# decoder.net
KiCad netlist of a schematic drawn in EAGLE
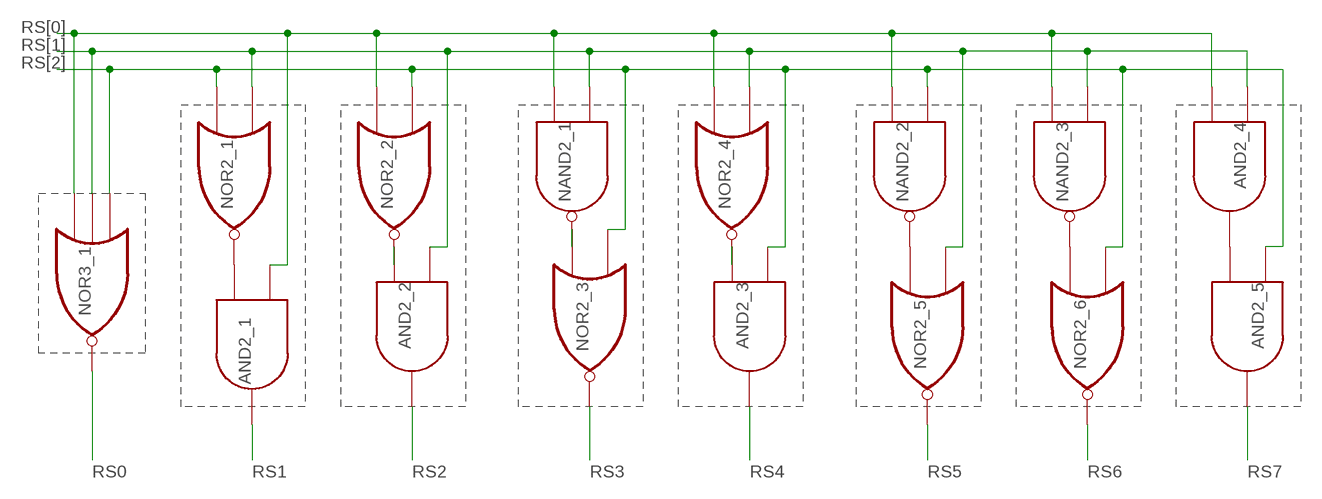
[diagram p0: schematic, sheet 1]

(export (version "E")
  (design (tool "Eeschema 10.0.6"))
  (components
    (comp (ref "AND2_1")
      (value "AND2")
      (footprint "eagle-import:3PIN")
      (libsource (lib "eagle-import") (part "AND2"))
    )
    (comp (ref "AND2_2")
      (value "AND2")
      (footprint "eagle-import:3PIN")
      (libsource (lib "eagle-import") (part "AND2"))
    )
    (comp (ref "AND2_3")
      (value "AND2")
      (footprint "eagle-import:3PIN")
      (libsource (lib "eagle-import") (part "AND2"))
    )
    (comp (ref "AND2_4")
      (value "AND2")
      (footprint "eagle-import:3PIN")
      (libsource (lib "eagle-import") (part "AND2"))
    )
    (comp (ref "AND2_5")
      (value "AND2")
      (footprint "eagle-import:3PIN")
      (libsource (lib "eagle-import") (part "AND2"))
    )
    (comp (ref "NAND2_1")
      (value "NAND2")
      (footprint "eagle-import:3PIN")
      (libsource (lib "eagle-import") (part "NAND2"))
    )
    (comp (ref "NAND2_2")
      (value "NAND2")
      (footprint "eagle-import:3PIN")
      (libsource (lib "eagle-import") (part "NAND2"))
    )
    (comp (ref "NAND2_3")
      (value "NAND2")
      (footprint "eagle-import:3PIN")
      (libsource (lib "eagle-import") (part "NAND2"))
    )
    (comp (ref "NOR2_1")
      (value "NOR2")
      (footprint "eagle-import:3PIN")
      (libsource (lib "eagle-import") (part "NOR2"))
    )
    (comp (ref "NOR2_2")
      (value "NOR2")
      (footprint "eagle-import:3PIN")
      (libsource (lib "eagle-import") (part "NOR2"))
    )
    (comp (ref "NOR2_3")
      (value "NOR2")
      (footprint "eagle-import:3PIN")
      (libsource (lib "eagle-import") (part "NOR2"))
    )
    (comp (ref "NOR2_4")
      (value "NOR2")
      (footprint "eagle-import:3PIN")
      (libsource (lib "eagle-import") (part "NOR2"))
    )
    (comp (ref "NOR2_5")
      (value "NOR2")
      (footprint "eagle-import:3PIN")
      (libsource (lib "eagle-import") (part "NOR2"))
    )
    (comp (ref "NOR2_6")
      (value "NOR2")
      (footprint "eagle-import:3PIN")
      (libsource (lib "eagle-import") (part "NOR2"))
    )
    (comp (ref "NOR3_1")
      (value "NOR3")
      (footprint "eagle-import:5PIN")
      (libsource (lib "eagle-import") (part "NOR3"))
    )
  )
  (nets
    (net (code "1") (name "/RS0") (class "Default")
      (node (ref "NOR3_1") (pin "P$4") (pinfunction "O_P$4") (pintype "output"))
    )
    (net (code "2") (name "/RS1") (class "Default")
      (node (ref "AND2_1") (pin "P$3") (pinfunction "O_P$3") (pintype "output"))
    )
    (net (code "3") (name "/RS2") (class "Default")
      (node (ref "AND2_2") (pin "P$3") (pinfunction "O_P$3") (pintype "output"))
    )
    (net (code "4") (name "/RS3") (class "Default")
      (node (ref "NOR2_3") (pin "P$3") (pinfunction "O_P$3") (pintype "output"))
    )
    (net (code "5") (name "/RS4") (class "Default")
      (node (ref "AND2_3") (pin "P$3") (pinfunction "O_P$3") (pintype "output"))
    )
    (net (code "6") (name "/RS5") (class "Default")
      (node (ref "NOR2_5") (pin "P$3") (pinfunction "O_P$3") (pintype "output"))
    )
    (net (code "7") (name "/RS6") (class "Default")
      (node (ref "NOR2_6") (pin "P$3") (pinfunction "O_P$3") (pintype "output"))
    )
    (net (code "8") (name "/RS7") (class "Default")
      (node (ref "AND2_5") (pin "P$3") (pinfunction "O_P$3") (pintype "output"))
    )
    (net (code "9") (name "/RS[0]") (class "Default")
      (node (ref "AND2_1") (pin "P$1") (pinfunction "A_P$1") (pintype "input"))
      (node (ref "AND2_4") (pin "P$2") (pinfunction "I1_P$2") (pintype "input"))
      (node (ref "NAND2_1") (pin "P$2") (pinfunction "I1_P$2") (pintype "input"))
      (node (ref "NAND2_2") (pin "P$2") (pinfunction "I1_P$2") (pintype "input"))
      (node (ref "NAND2_3") (pin "P$2") (pinfunction "I1_P$2") (pintype "input"))
      (node (ref "NOR2_2") (pin "P$2") (pinfunction "I1_P$2") (pintype "input"))
      (node (ref "NOR2_4") (pin "P$2") (pinfunction "I1_P$2") (pintype "input"))
      (node (ref "NOR3_1") (pin "P$2") (pinfunction "I1_P$2") (pintype "input"))
    )
    (net (code "10") (name "/RS[1]") (class "Default")
      (node (ref "AND2_2") (pin "P$1") (pinfunction "A_P$1") (pintype "input"))
      (node (ref "AND2_4") (pin "P$1") (pinfunction "A_P$1") (pintype "input"))
      (node (ref "NAND2_1") (pin "P$1") (pinfunction "A_P$1") (pintype "input"))
      (node (ref "NAND2_3") (pin "P$1") (pinfunction "A_P$1") (pintype "input"))
      (node (ref "NOR2_1") (pin "P$1") (pinfunction "I0_P$1") (pintype "input"))
      (node (ref "NOR2_4") (pin "P$1") (pinfunction "I0_P$1") (pintype "input"))
      (node (ref "NOR2_5") (pin "P$1") (pinfunction "I0_P$1") (pintype "input"))
      (node (ref "NOR3_1") (pin "P$3") (pinfunction "I2_P$3") (pintype "input"))
    )
    (net (code "11") (name "/RS[2]") (class "Default")
      (node (ref "AND2_3") (pin "P$1") (pinfunction "A_P$1") (pintype "input"))
      (node (ref "AND2_5") (pin "P$1") (pinfunction "A_P$1") (pintype "input"))
      (node (ref "NAND2_2") (pin "P$1") (pinfunction "A_P$1") (pintype "input"))
      (node (ref "NOR2_1") (pin "P$2") (pinfunction "I1_P$2") (pintype "input"))
      (node (ref "NOR2_2") (pin "P$1") (pinfunction "I0_P$1") (pintype "input"))
      (node (ref "NOR2_3") (pin "P$1") (pinfunction "I0_P$1") (pintype "input"))
      (node (ref "NOR2_6") (pin "P$1") (pinfunction "I0_P$1") (pintype "input"))
      (node (ref "NOR3_1") (pin "P$1") (pinfunction "I0_P$1") (pintype "input"))
    )
    (net (code "12") (name "Net-(AND2_1-I1)") (class "Default")
      (node (ref "AND2_1") (pin "P$2") (pinfunction "I1_P$2") (pintype "input"))
      (node (ref "NOR2_1") (pin "P$3") (pinfunction "O_P$3") (pintype "output"))
    )
    (net (code "13") (name "Net-(AND2_2-I1)") (class "Default")
      (node (ref "AND2_2") (pin "P$2") (pinfunction "I1_P$2") (pintype "input"))
      (node (ref "NOR2_2") (pin "P$3") (pinfunction "O_P$3") (pintype "output"))
    )
    (net (code "14") (name "Net-(AND2_3-I1)") (class "Default")
      (node (ref "AND2_3") (pin "P$2") (pinfunction "I1_P$2") (pintype "input"))
      (node (ref "NOR2_4") (pin "P$3") (pinfunction "O_P$3") (pintype "output"))
    )
    (net (code "15") (name "Net-(AND2_4-O)") (class "Default")
      (node (ref "AND2_4") (pin "P$3") (pinfunction "O_P$3") (pintype "output"))
      (node (ref "AND2_5") (pin "P$2") (pinfunction "I1_P$2") (pintype "input"))
    )
    (net (code "16") (name "Net-(NAND2_1-O)") (class "Default")
      (node (ref "NAND2_1") (pin "P$3") (pinfunction "O_P$3") (pintype "output"))
      (node (ref "NOR2_3") (pin "P$2") (pinfunction "I1_P$2") (pintype "input"))
    )
    (net (code "17") (name "Net-(NAND2_2-O)") (class "Default")
      (node (ref "NAND2_2") (pin "P$3") (pinfunction "O_P$3") (pintype "output"))
      (node (ref "NOR2_5") (pin "P$2") (pinfunction "I1_P$2") (pintype "input"))
    )
    (net (code "18") (name "Net-(NAND2_3-O)") (class "Default")
      (node (ref "NAND2_3") (pin "P$3") (pinfunction "O_P$3") (pintype "output"))
      (node (ref "NOR2_6") (pin "P$2") (pinfunction "I1_P$2") (pintype "input"))
    )
  )
)
